# HW3.net
KiCad netlist of a schematic drawn in EAGLE
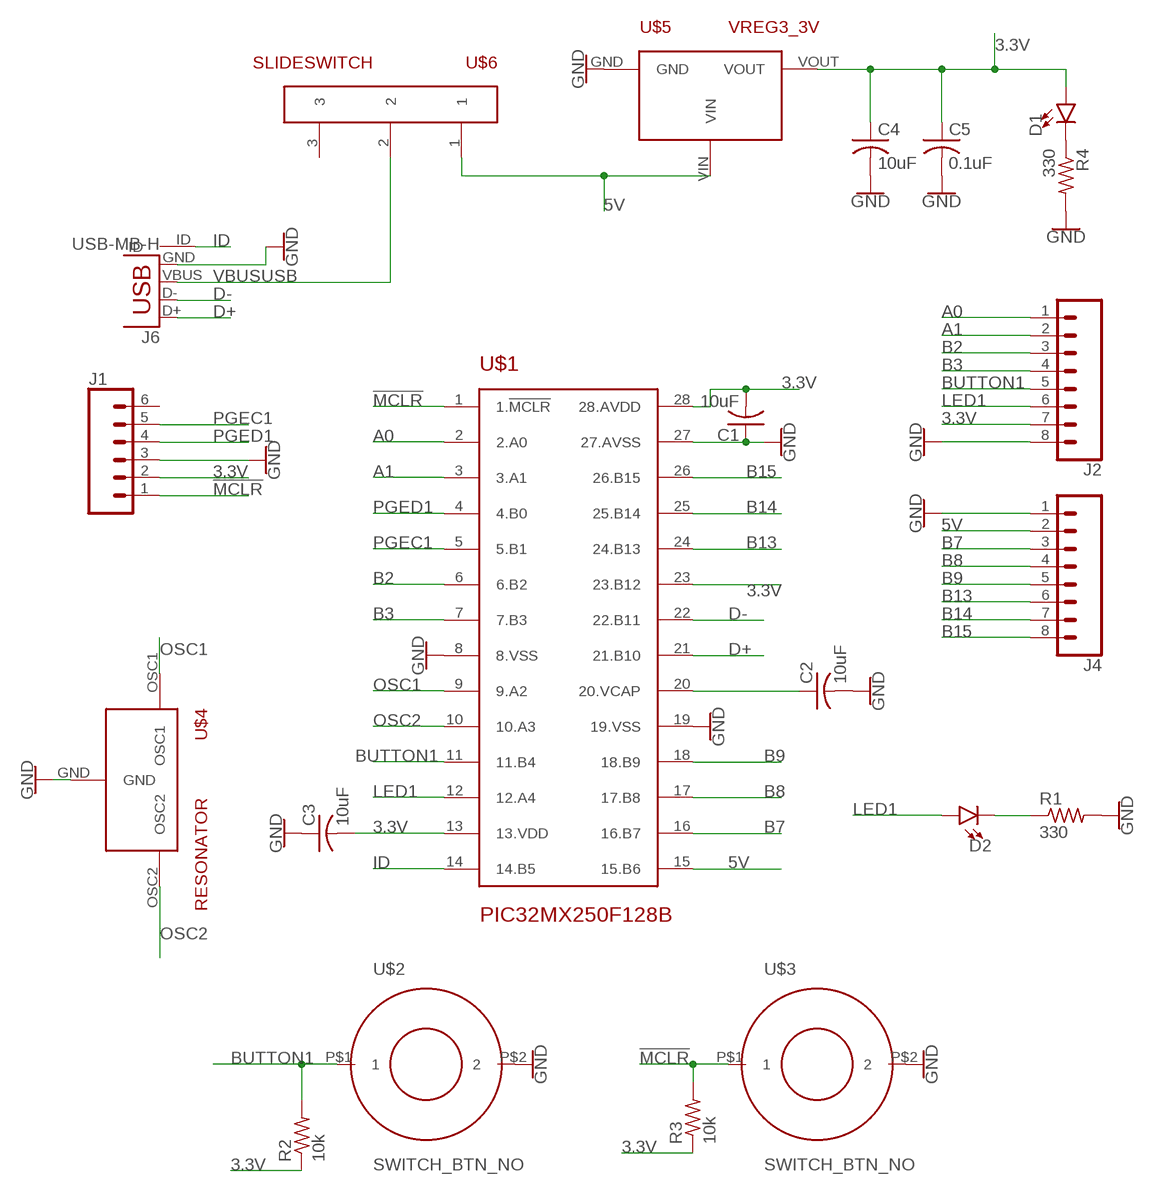
[diagram p0: schematic, sheet 1]

(export (version "E")
  (design (tool "Eeschema 10.0.6"))
  (components
    (comp (ref "C1")
      (value "10uF")
      (footprint "eagle-import:C025-024X044")
      (libsource (lib "eagle-import") (part "C-US025-024X044"))
    )
    (comp (ref "C2")
      (value "10uF")
      (footprint "eagle-import:C025-024X044")
      (libsource (lib "eagle-import") (part "C-US025-024X044"))
    )
    (comp (ref "C3")
      (value "10uF")
      (footprint "eagle-import:C025-024X044")
      (libsource (lib "eagle-import") (part "C-US025-024X044"))
    )
    (comp (ref "C4")
      (value "10uF")
      (footprint "eagle-import:C025-024X044")
      (libsource (lib "eagle-import") (part "C-US025-024X044"))
    )
    (comp (ref "C5")
      (value "0.1uF")
      (footprint "eagle-import:C025-024X044")
      (libsource (lib "eagle-import") (part "C-US025-024X044"))
    )
    (comp (ref "D1")
      (value "LED3MM")
      (footprint "eagle-import:LED_3MM")
      (libsource (lib "eagle-import") (part "LED3MM"))
    )
    (comp (ref "D2")
      (value "LED3MM")
      (footprint "eagle-import:LED_3MM")
      (libsource (lib "eagle-import") (part "LED3MM"))
    )
    (comp (ref "J1")
      (value "CONN_06SILK_FEMALE_PTH")
      (footprint "eagle-import:1X06")
      (libsource (lib "eagle-import") (part "CONN_06SILK_FEMALE_PTH"))
    )
    (comp (ref "J2")
      (value "CONN_08\"")
      (footprint "eagle-import:1X08")
      (libsource (lib "eagle-import") (part "CONN_08{dblquote}"))
    )
    (comp (ref "J4")
      (value "CONN_08\"")
      (footprint "eagle-import:1X08")
      (libsource (lib "eagle-import") (part "CONN_08{dblquote}"))
    )
    (comp (ref "J6")
      (value "USB-MB-H")
      (footprint "eagle-import:USB-MB-H")
      (libsource (lib "eagle-import") (part "USB-MB-H"))
    )
    (comp (ref "R1")
      (value "330")
      (footprint "eagle-import:0204_7")
      (libsource (lib "eagle-import") (part "R-US_0204/7"))
    )
    (comp (ref "R2")
      (value "10k")
      (footprint "eagle-import:0204_7")
      (libsource (lib "eagle-import") (part "R-US_0204/7"))
    )
    (comp (ref "R3")
      (value "10k")
      (footprint "eagle-import:0204_7")
      (libsource (lib "eagle-import") (part "R-US_0204/7"))
    )
    (comp (ref "R4")
      (value "330")
      (footprint "eagle-import:0204_7")
      (libsource (lib "eagle-import") (part "R-US_0204/7"))
    )
    (comp (ref "U$1")
      (value "PIC32MX250F128B")
      (footprint "eagle-import:DIL28-3")
      (libsource (lib "eagle-import") (part "PIC32MX250F128B"))
    )
    (comp (ref "U$2")
      (value "SWITCH_BTN_NO")
      (footprint "eagle-import:BTN_2")
      (libsource (lib "eagle-import") (part "SWITCH_BTN_NO"))
    )
    (comp (ref "U$3")
      (value "SWITCH_BTN_NO")
      (footprint "eagle-import:BTN_2")
      (libsource (lib "eagle-import") (part "SWITCH_BTN_NO"))
    )
    (comp (ref "U$4")
      (value "RESONATOR")
      (footprint "eagle-import:1X3")
      (libsource (lib "eagle-import") (part "RESONATOR"))
    )
    (comp (ref "U$5")
      (value "VREG3_3V")
      (footprint "eagle-import:1X3_VREG")
      (libsource (lib "eagle-import") (part "VREG3_3V"))
    )
    (comp (ref "U$6")
      (value "SLIDESWITCH")
      (footprint "eagle-import:SWITCH")
      (libsource (lib "eagle-import") (part "SLIDESWITCH"))
    )
  )
  (nets
    (net (code "1") (name "/3.3V") (class "Default")
      (node (ref "C1") (pin "2") (pinfunction "2_2") (pintype "passive"))
      (node (ref "C3") (pin "2") (pinfunction "2_2") (pintype "passive"))
      (node (ref "C4") (pin "1") (pinfunction "1_1") (pintype "passive"))
      (node (ref "C5") (pin "1") (pinfunction "1_1") (pintype "passive"))
      (node (ref "D1") (pin "A") (pinfunction "A_A") (pintype "passive"))
      (node (ref "J1") (pin "2") (pinfunction "2_2") (pintype "passive"))
      (node (ref "J2") (pin "7") (pinfunction "7_7") (pintype "passive"))
      (node (ref "R2") (pin "1") (pinfunction "1_1") (pintype "passive"))
      (node (ref "R3") (pin "1") (pinfunction "1_1") (pintype "passive"))
      (node (ref "U$1") (pin "13") (pinfunction "13.VDD_13") (pintype "bidirectional"))
      (node (ref "U$1") (pin "23") (pinfunction "23.B12_23") (pintype "bidirectional"))
      (node (ref "U$1") (pin "28") (pinfunction "28.AVDD_28") (pintype "bidirectional"))
      (node (ref "U$5") (pin "VOUT") (pinfunction "VOUT_VOUT") (pintype "bidirectional"))
    )
    (net (code "2") (name "/5V") (class "Default")
      (node (ref "J4") (pin "2") (pinfunction "2_2") (pintype "passive"))
      (node (ref "U$1") (pin "15") (pinfunction "15.B6_15") (pintype "bidirectional"))
      (node (ref "U$5") (pin "VIN") (pinfunction "VIN_VIN") (pintype "bidirectional"))
      (node (ref "U$6") (pin "1") (pinfunction "1_1") (pintype "bidirectional"))
    )
    (net (code "3") (name "/A0") (class "Default")
      (node (ref "J2") (pin "1") (pinfunction "1_1") (pintype "passive"))
      (node (ref "U$1") (pin "2") (pinfunction "2.A0_2") (pintype "bidirectional"))
    )
    (net (code "4") (name "/A1") (class "Default")
      (node (ref "J2") (pin "2") (pinfunction "2_2") (pintype "passive"))
      (node (ref "U$1") (pin "3") (pinfunction "3.A1_3") (pintype "bidirectional"))
    )
    (net (code "5") (name "/B2") (class "Default")
      (node (ref "J2") (pin "3") (pinfunction "3_3") (pintype "passive"))
      (node (ref "U$1") (pin "6") (pinfunction "6.B2_6") (pintype "bidirectional"))
    )
    (net (code "6") (name "/B3") (class "Default")
      (node (ref "J2") (pin "4") (pinfunction "4_4") (pintype "passive"))
      (node (ref "U$1") (pin "7") (pinfunction "7.B3_7") (pintype "bidirectional"))
    )
    (net (code "7") (name "/B7") (class "Default")
      (node (ref "J4") (pin "3") (pinfunction "3_3") (pintype "passive"))
      (node (ref "U$1") (pin "16") (pinfunction "16.B7_16") (pintype "bidirectional"))
    )
    (net (code "8") (name "/B8") (class "Default")
      (node (ref "J4") (pin "4") (pinfunction "4_4") (pintype "passive"))
      (node (ref "U$1") (pin "17") (pinfunction "17.B8_17") (pintype "bidirectional"))
    )
    (net (code "9") (name "/B9") (class "Default")
      (node (ref "J4") (pin "5") (pinfunction "5_5") (pintype "passive"))
      (node (ref "U$1") (pin "18") (pinfunction "18.B9_18") (pintype "bidirectional"))
    )
    (net (code "10") (name "/B13") (class "Default")
      (node (ref "J4") (pin "6") (pinfunction "6_6") (pintype "passive"))
      (node (ref "U$1") (pin "24") (pinfunction "24.B13_24") (pintype "bidirectional"))
    )
    (net (code "11") (name "/B14") (class "Default")
      (node (ref "J4") (pin "7") (pinfunction "7_7") (pintype "passive"))
      (node (ref "U$1") (pin "25") (pinfunction "25.B14_25") (pintype "bidirectional"))
    )
    (net (code "12") (name "/B15") (class "Default")
      (node (ref "J4") (pin "8") (pinfunction "8_8") (pintype "passive"))
      (node (ref "U$1") (pin "26") (pinfunction "26.B15_26") (pintype "bidirectional"))
    )
    (net (code "13") (name "/BUTTON1") (class "Default")
      (node (ref "J2") (pin "5") (pinfunction "5_5") (pintype "passive"))
      (node (ref "R2") (pin "2") (pinfunction "2_2") (pintype "passive"))
      (node (ref "U$1") (pin "11") (pinfunction "11.B4_11") (pintype "bidirectional"))
      (node (ref "U$2") (pin "P$1") (pinfunction "1_P$1") (pintype "bidirectional"))
    )
    (net (code "14") (name "/D+") (class "Default")
      (node (ref "J6") (pin "D+") (pinfunction "D+_D+") (pintype "bidirectional"))
      (node (ref "U$1") (pin "21") (pinfunction "21.B10_21") (pintype "bidirectional"))
    )
    (net (code "15") (name "/D-") (class "Default")
      (node (ref "J6") (pin "D-") (pinfunction "D-_D-") (pintype "bidirectional"))
      (node (ref "U$1") (pin "22") (pinfunction "22.B11_22") (pintype "bidirectional"))
    )
    (net (code "16") (name "/ID") (class "Default")
      (node (ref "J6") (pin "ID") (pinfunction "ID_ID") (pintype "bidirectional"))
      (node (ref "U$1") (pin "14") (pinfunction "14.B5_14") (pintype "bidirectional"))
    )
    (net (code "17") (name "/LED1") (class "Default")
      (node (ref "D2") (pin "A") (pinfunction "A_A") (pintype "passive"))
      (node (ref "J2") (pin "6") (pinfunction "6_6") (pintype "passive"))
      (node (ref "U$1") (pin "12") (pinfunction "12.A4_12") (pintype "bidirectional"))
    )
    (net (code "18") (name "/OSC1") (class "Default")
      (node (ref "U$1") (pin "9") (pinfunction "9.A2_9") (pintype "bidirectional"))
      (node (ref "U$4") (pin "OSC1") (pinfunction "OSC1_OSC1") (pintype "bidirectional"))
    )
    (net (code "19") (name "/OSC2") (class "Default")
      (node (ref "U$1") (pin "10") (pinfunction "10.A3_10") (pintype "bidirectional"))
      (node (ref "U$4") (pin "OSC2") (pinfunction "OSC2_OSC2") (pintype "bidirectional"))
    )
    (net (code "20") (name "/PGEC1") (class "Default")
      (node (ref "J1") (pin "5") (pinfunction "5_5") (pintype "passive"))
      (node (ref "U$1") (pin "5") (pinfunction "5.B1_5") (pintype "bidirectional"))
    )
    (net (code "21") (name "/PGED1") (class "Default")
      (node (ref "J1") (pin "4") (pinfunction "4_4") (pintype "passive"))
      (node (ref "U$1") (pin "4") (pinfunction "4.B0_4") (pintype "bidirectional"))
    )
    (net (code "22") (name "/VBUSUSB") (class "Default")
      (node (ref "J6") (pin "VBUS") (pinfunction "VBUS_VBUS") (pintype "bidirectional"))
      (node (ref "U$6") (pin "2") (pinfunction "2_2") (pintype "bidirectional"))
    )
    (net (code "23") (name "/~{MCLR}") (class "Default")
      (node (ref "J1") (pin "1") (pinfunction "1_1") (pintype "passive"))
      (node (ref "R3") (pin "2") (pinfunction "2_2") (pintype "passive"))
      (node (ref "U$1") (pin "1") (pinfunction "1.~{MCLR}_1") (pintype "bidirectional"))
      (node (ref "U$3") (pin "P$1") (pinfunction "1_P$1") (pintype "bidirectional"))
    )
    (net (code "24") (name "GND") (class "Default")
      (node (ref "C1") (pin "1") (pinfunction "1_1") (pintype "passive"))
      (node (ref "C2") (pin "2") (pinfunction "2_2") (pintype "passive"))
      (node (ref "C3") (pin "1") (pinfunction "1_1") (pintype "passive"))
      (node (ref "C4") (pin "2") (pinfunction "2_2") (pintype "passive"))
      (node (ref "C5") (pin "2") (pinfunction "2_2") (pintype "passive"))
      (node (ref "J1") (pin "3") (pinfunction "3_3") (pintype "passive"))
      (node (ref "J2") (pin "8") (pinfunction "8_8") (pintype "passive"))
      (node (ref "J4") (pin "1") (pinfunction "1_1") (pintype "passive"))
      (node (ref "J6") (pin "GND") (pinfunction "GND_GND") (pintype "bidirectional"))
      (node (ref "R1") (pin "2") (pinfunction "2_2") (pintype "passive"))
      (node (ref "R4") (pin "2") (pinfunction "2_2") (pintype "passive"))
      (node (ref "U$1") (pin "19") (pinfunction "19.VSS_19") (pintype "bidirectional"))
      (node (ref "U$1") (pin "27") (pinfunction "27.AVSS_27") (pintype "bidirectional"))
      (node (ref "U$1") (pin "8") (pinfunction "8.VSS_8") (pintype "bidirectional"))
      (node (ref "U$2") (pin "P$2") (pinfunction "2_P$2") (pintype "bidirectional"))
      (node (ref "U$3") (pin "P$2") (pinfunction "2_P$2") (pintype "bidirectional"))
      (node (ref "U$4") (pin "GND") (pinfunction "GND_GND") (pintype "bidirectional"))
      (node (ref "U$5") (pin "GND") (pinfunction "GND_GND") (pintype "bidirectional"))
    )
    (net (code "25") (name "Net-(D1-C)") (class "Default")
      (node (ref "D1") (pin "K") (pinfunction "C_K") (pintype "passive"))
      (node (ref "R4") (pin "1") (pinfunction "1_1") (pintype "passive"))
    )
    (net (code "26") (name "Net-(D2-C)") (class "Default")
      (node (ref "D2") (pin "K") (pinfunction "C_K") (pintype "passive"))
      (node (ref "R1") (pin "1") (pinfunction "1_1") (pintype "passive"))
    )
    (net (code "27") (name "Net-(U$1-20.VCAP)") (class "Default")
      (node (ref "C2") (pin "1") (pinfunction "1_1") (pintype "passive"))
      (node (ref "U$1") (pin "20") (pinfunction "20.VCAP_20") (pintype "bidirectional"))
    )
    (net (code "28") (name "unconnected-(J1-Pad6)") (class "Default")
      (node (ref "J1") (pin "6") (pinfunction "6_6") (pintype "passive"))
    )
    (net (code "29") (name "unconnected-(U$6-Pad3)") (class "Default")
      (node (ref "U$6") (pin "3") (pinfunction "3_3") (pintype "bidirectional"))
    )
  )
)
